# spi2par2019faithful.net
KiCad netlist of a schematic drawn in EAGLE
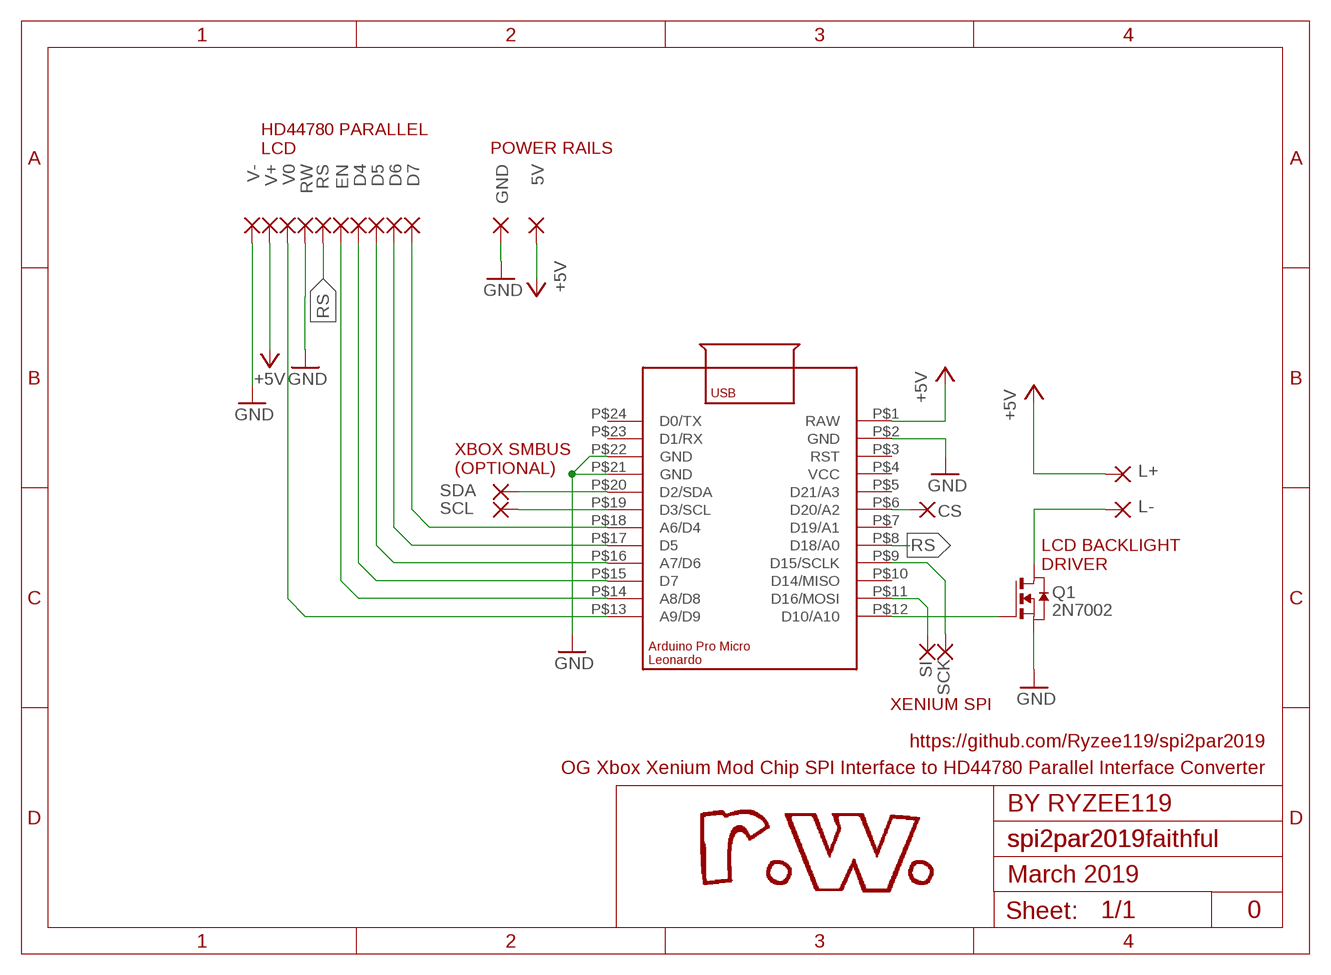
[diagram p0: schematic, sheet 1]

(export (version "E")
  (design (tool "Eeschema 10.0.6"))
  (components
    (comp (ref "5V")
      (value "WIREPADSMD1,27-254")
      (footprint "eagle-import:SMD1,27-2,54")
      (libsource (lib "eagle-import") (part "WIREPADSMD1,27-254"))
    )
    (comp (ref "CS")
      (value "WIREPADSMD1,27-254")
      (footprint "eagle-import:SMD1,27-2,54")
      (libsource (lib "eagle-import") (part "WIREPADSMD1,27-254"))
    )
    (comp (ref "D4")
      (value "WIREPADSMD1,27-254")
      (footprint "eagle-import:SMD1,27-2,54")
      (libsource (lib "eagle-import") (part "WIREPADSMD1,27-254"))
    )
    (comp (ref "D5")
      (value "WIREPADSMD1,27-254")
      (footprint "eagle-import:SMD1,27-2,54")
      (libsource (lib "eagle-import") (part "WIREPADSMD1,27-254"))
    )
    (comp (ref "D6")
      (value "WIREPADSMD1,27-254")
      (footprint "eagle-import:SMD1,27-2,54")
      (libsource (lib "eagle-import") (part "WIREPADSMD1,27-254"))
    )
    (comp (ref "D7")
      (value "WIREPADSMD1,27-254")
      (footprint "eagle-import:SMD1,27-2,54")
      (libsource (lib "eagle-import") (part "WIREPADSMD1,27-254"))
    )
    (comp (ref "EN")
      (value "WIREPADSMD1,27-254")
      (footprint "eagle-import:SMD1,27-2,54")
      (libsource (lib "eagle-import") (part "WIREPADSMD1,27-254"))
    )
    (comp (ref "GND")
      (value "WIREPADSMD1,27-254")
      (footprint "eagle-import:SMD1,27-2,54")
      (libsource (lib "eagle-import") (part "WIREPADSMD1,27-254"))
    )
    (comp (ref "L+")
      (value "WIREPADSMD1,27-254")
      (footprint "eagle-import:SMD1,27-2,54")
      (libsource (lib "eagle-import") (part "WIREPADSMD1,27-254"))
    )
    (comp (ref "L-")
      (value "WIREPADSMD1,27-254")
      (footprint "eagle-import:SMD1,27-2,54")
      (libsource (lib "eagle-import") (part "WIREPADSMD1,27-254"))
    )
    (comp (ref "Q1")
      (value "2N70026Ω")
      (footprint "eagle-import:SOT-23")
      (libsource (lib "eagle-import") (part "NMOSSOT23"))
    )
    (comp (ref "RS")
      (value "WIREPADSMD1,27-254")
      (footprint "eagle-import:SMD1,27-2,54")
      (libsource (lib "eagle-import") (part "WIREPADSMD1,27-254"))
    )
    (comp (ref "RW")
      (value "WIREPADSMD1,27-254")
      (footprint "eagle-import:SMD1,27-2,54")
      (libsource (lib "eagle-import") (part "WIREPADSMD1,27-254"))
    )
    (comp (ref "SCK")
      (value "WIREPADSMD1,27-254")
      (footprint "eagle-import:SMD1,27-2,54")
      (libsource (lib "eagle-import") (part "WIREPADSMD1,27-254"))
    )
    (comp (ref "SCL")
      (value "WIREPADSMD1,27-254")
      (footprint "eagle-import:SMD1,27-2,54")
      (libsource (lib "eagle-import") (part "WIREPADSMD1,27-254"))
    )
    (comp (ref "SDA")
      (value "WIREPADSMD1,27-254")
      (footprint "eagle-import:SMD1,27-2,54")
      (libsource (lib "eagle-import") (part "WIREPADSMD1,27-254"))
    )
    (comp (ref "SI")
      (value "WIREPADSMD1,27-254")
      (footprint "eagle-import:SMD1,27-2,54")
      (libsource (lib "eagle-import") (part "WIREPADSMD1,27-254"))
    )
    (comp (ref "U1")
      (value "ARDUINO_LEONARDO_MICRO")
      (footprint "eagle-import:ARDUINO_LEONARDO_MICRO")
      (libsource (lib "eagle-import") (part "ARDUINO_LEONARDO_MICRO"))
    )
    (comp (ref "V+")
      (value "WIREPADSMD1,27-254")
      (footprint "eagle-import:SMD1,27-2,54")
      (libsource (lib "eagle-import") (part "WIREPADSMD1,27-254"))
    )
    (comp (ref "V-")
      (value "WIREPADSMD1,27-254")
      (footprint "eagle-import:SMD1,27-2,54")
      (libsource (lib "eagle-import") (part "WIREPADSMD1,27-254"))
    )
    (comp (ref "V0")
      (value "WIREPADSMD1,27-254")
      (footprint "eagle-import:SMD1,27-2,54")
      (libsource (lib "eagle-import") (part "WIREPADSMD1,27-254"))
    )
  )
  (nets
    (net (code "1") (name "+5V") (class "Default")
      (node (ref "5V") (pin "1") (pinfunction "P_1") (pintype "passive"))
      (node (ref "L+") (pin "1") (pinfunction "P_1") (pintype "passive"))
      (node (ref "U1") (pin "P$1") (pinfunction "RAW_P$1") (pintype "bidirectional"))
      (node (ref "V+") (pin "1") (pinfunction "P_1") (pintype "passive"))
    )
    (net (code "2") (name "GND") (class "Default")
      (node (ref "GND") (pin "1") (pinfunction "P_1") (pintype "passive"))
      (node (ref "Q1") (pin "2") (pinfunction "S_2") (pintype "passive"))
      (node (ref "RW") (pin "1") (pinfunction "P_1") (pintype "passive"))
      (node (ref "U1") (pin "P$2") (pinfunction "GND_P$2") (pintype "bidirectional"))
      (node (ref "U1") (pin "P$21") (pinfunction "GND_P$21") (pintype "bidirectional"))
      (node (ref "U1") (pin "P$22") (pinfunction "GND_P$22") (pintype "bidirectional"))
      (node (ref "V-") (pin "1") (pinfunction "P_1") (pintype "passive"))
    )
    (net (code "3") (name "Net-(CS-P)") (class "Default")
      (node (ref "CS") (pin "1") (pinfunction "P_1") (pintype "passive"))
      (node (ref "U1") (pin "P$6") (pinfunction "D20/A2_P$6") (pintype "bidirectional"))
    )
    (net (code "4") (name "Net-(D4-P)") (class "Default")
      (node (ref "D4") (pin "1") (pinfunction "P_1") (pintype "passive"))
      (node (ref "U1") (pin "P$15") (pinfunction "D7_P$15") (pintype "bidirectional"))
    )
    (net (code "5") (name "Net-(D5-P)") (class "Default")
      (node (ref "D5") (pin "1") (pinfunction "P_1") (pintype "passive"))
      (node (ref "U1") (pin "P$16") (pinfunction "A7/D6_P$16") (pintype "bidirectional"))
    )
    (net (code "6") (name "Net-(D6-P)") (class "Default")
      (node (ref "D6") (pin "1") (pinfunction "P_1") (pintype "passive"))
      (node (ref "U1") (pin "P$17") (pinfunction "D5_P$17") (pintype "bidirectional"))
    )
    (net (code "7") (name "Net-(D7-P)") (class "Default")
      (node (ref "D7") (pin "1") (pinfunction "P_1") (pintype "passive"))
      (node (ref "U1") (pin "P$18") (pinfunction "A6/D4_P$18") (pintype "bidirectional"))
    )
    (net (code "8") (name "Net-(EN-P)") (class "Default")
      (node (ref "EN") (pin "1") (pinfunction "P_1") (pintype "passive"))
      (node (ref "U1") (pin "P$14") (pinfunction "A8/D8_P$14") (pintype "bidirectional"))
    )
    (net (code "9") (name "Net-(L--P)") (class "Default")
      (node (ref "L-") (pin "1") (pinfunction "P_1") (pintype "passive"))
      (node (ref "Q1") (pin "1") (pinfunction "D_1") (pintype "passive"))
    )
    (net (code "10") (name "Net-(Q1-G)") (class "Default")
      (node (ref "Q1") (pin "3") (pinfunction "G_3") (pintype "passive"))
      (node (ref "U1") (pin "P$12") (pinfunction "D10/A10_P$12") (pintype "bidirectional"))
    )
    (net (code "11") (name "Net-(SCK-P)") (class "Default")
      (node (ref "SCK") (pin "1") (pinfunction "P_1") (pintype "passive"))
      (node (ref "U1") (pin "P$9") (pinfunction "D15/SCLK_P$9") (pintype "bidirectional"))
    )
    (net (code "12") (name "Net-(SCL-P)") (class "Default")
      (node (ref "SCL") (pin "1") (pinfunction "P_1") (pintype "passive"))
      (node (ref "U1") (pin "P$19") (pinfunction "D3/SCL_P$19") (pintype "bidirectional"))
    )
    (net (code "13") (name "Net-(SDA-P)") (class "Default")
      (node (ref "SDA") (pin "1") (pinfunction "P_1") (pintype "passive"))
      (node (ref "U1") (pin "P$20") (pinfunction "D2/SDA_P$20") (pintype "bidirectional"))
    )
    (net (code "14") (name "Net-(SI-P)") (class "Default")
      (node (ref "SI") (pin "1") (pinfunction "P_1") (pintype "passive"))
      (node (ref "U1") (pin "P$11") (pinfunction "D16/MOSI_P$11") (pintype "bidirectional"))
    )
    (net (code "15") (name "Net-(U1-A9{slash}D9)") (class "Default")
      (node (ref "U1") (pin "P$13") (pinfunction "A9/D9_P$13") (pintype "bidirectional"))
      (node (ref "V0") (pin "1") (pinfunction "P_1") (pintype "passive"))
    )
    (net (code "16") (name "RS") (class "Default")
      (node (ref "RS") (pin "1") (pinfunction "P_1") (pintype "passive"))
      (node (ref "U1") (pin "P$8") (pinfunction "D18/A0_P$8") (pintype "bidirectional"))
    )
    (net (code "17") (name "unconnected-(U1-D0{slash}TX-PadP$24)") (class "Default")
      (node (ref "U1") (pin "P$24") (pinfunction "D0/TX_P$24") (pintype "bidirectional"))
    )
    (net (code "18") (name "unconnected-(U1-D1{slash}RX-PadP$23)") (class "Default")
      (node (ref "U1") (pin "P$23") (pinfunction "D1/RX_P$23") (pintype "bidirectional"))
    )
    (net (code "19") (name "unconnected-(U1-D14{slash}MISO-PadP$10)") (class "Default")
      (node (ref "U1") (pin "P$10") (pinfunction "D14/MISO_P$10") (pintype "bidirectional"))
    )
    (net (code "20") (name "unconnected-(U1-D19{slash}A1-PadP$7)") (class "Default")
      (node (ref "U1") (pin "P$7") (pinfunction "D19/A1_P$7") (pintype "bidirectional"))
    )
    (net (code "21") (name "unconnected-(U1-D21{slash}A3-PadP$5)") (class "Default")
      (node (ref "U1") (pin "P$5") (pinfunction "D21/A3_P$5") (pintype "bidirectional"))
    )
    (net (code "22") (name "unconnected-(U1-RST-PadP$3)") (class "Default")
      (node (ref "U1") (pin "P$3") (pinfunction "RST_P$3") (pintype "bidirectional"))
    )
    (net (code "23") (name "unconnected-(U1-VCC-PadP$4)") (class "Default")
      (node (ref "U1") (pin "P$4") (pinfunction "VCC_P$4") (pintype "bidirectional"))
    )
  )
)
